# ICM-20948.net
KiCad netlist of a schematic drawn in Altium Designer
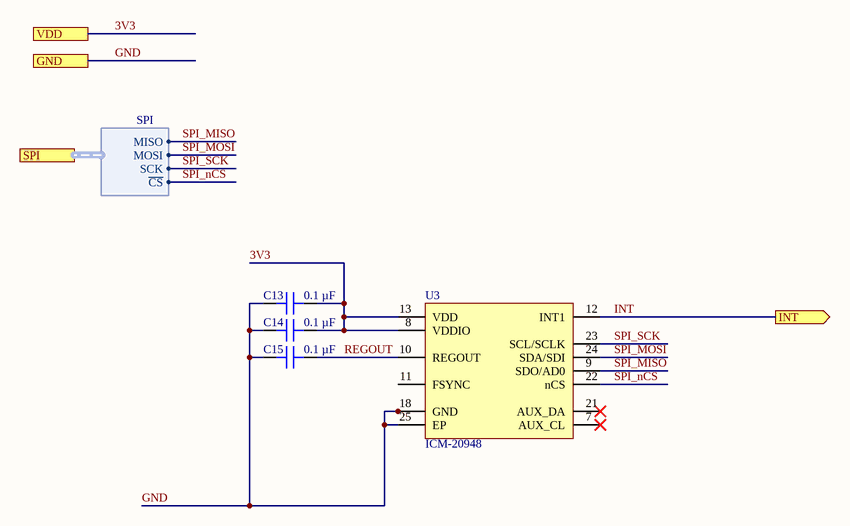
[diagram p0: ICM-20948.SchDoc]

(export (version "E")
  (design (tool "Eeschema 10.0.6"))
  (components
    (comp (ref "C13")
      (value "0.1 µF")
      (footprint "CAP 0402_1005")
      (description "CAP CER 0.1UF 16V X7R 0402")
      (fields (field (name "PART NUMBER") "C0402C104K4RACAUTO") (field (name "MANUFACTURER") "KEMET"))
      (libsource (lib "Celestial Altium Library - altium_library") (part "Capacitor"))
    )
    (comp (ref "C14")
      (value "0.1 µF")
      (footprint "CAP 0402_1005")
      (description "CAP CER 0.1UF 16V X7R 0402")
      (fields (field (name "PART NUMBER") "C0402C104K4RACAUTO") (field (name "MANUFACTURER") "KEMET"))
      (libsource (lib "Celestial Altium Library - altium_library") (part "Capacitor"))
    )
    (comp (ref "C15")
      (value "0.1 µF")
      (footprint "CAP 0402_1005")
      (description "CAP CER 0.1UF 16V X7R 0402")
      (fields (field (name "PART NUMBER") "C0402C104K4RACAUTO") (field (name "MANUFACTURER") "KEMET"))
      (libsource (lib "Celestial Altium Library - altium_library") (part "Capacitor"))
    )
    (comp (ref "U3")
      (value "ICM-20948")
      (footprint "ICM-20948")
      (description "9-DOF IMU")
      (libsource (lib "IC") (part "ICM-20948"))
    )
  )
  (nets
    (net (code "2") (name "/3V3") (class "Default")
      (node (ref "C13") (pin "1") (pinfunction "1_1") (pintype "passive"))
      (node (ref "C14") (pin "1") (pinfunction "1_1") (pintype "passive"))
      (node (ref "U3") (pin "13") (pinfunction "VDD_13") (pintype "passive"))
      (node (ref "U3") (pin "8") (pinfunction "VDDIO_8") (pintype "passive"))
    )
    (net (code "3") (name "/GND") (class "Default")
      (node (ref "C13") (pin "2") (pinfunction "2_2") (pintype "passive"))
      (node (ref "C14") (pin "2") (pinfunction "2_2") (pintype "passive"))
      (node (ref "C15") (pin "2") (pinfunction "2_2") (pintype "passive"))
      (node (ref "U3") (pin "18") (pinfunction "GND_18") (pintype "passive"))
      (node (ref "U3") (pin "20") (pinfunction "GND_20") (pintype "passive"))
      (node (ref "U3") (pin "25") (pinfunction "EP_25") (pintype "passive"))
    )
    (net (code "4") (name "/INT") (class "Default")
      (node (ref "U3") (pin "12") (pinfunction "INT1_12") (pintype "passive"))
    )
    (net (code "5") (name "/REGOUT") (class "Default")
      (node (ref "C15") (pin "1") (pinfunction "1_1") (pintype "passive"))
      (node (ref "U3") (pin "10") (pinfunction "REGOUT_10") (pintype "passive"))
    )
    (net (code "6") (name "/SPI_MISO") (class "Default")
      (node (ref "U3") (pin "9") (pinfunction "SDO/AD0_9") (pintype "passive"))
    )
    (net (code "7") (name "/SPI_MOSI") (class "Default")
      (node (ref "U3") (pin "24") (pinfunction "SDA/SDI_24") (pintype "passive"))
    )
    (net (code "8") (name "/SPI_SCK") (class "Default")
      (node (ref "U3") (pin "23") (pinfunction "SCL/SCLK_23") (pintype "passive"))
    )
    (net (code "9") (name "/SPI_nCS") (class "Default")
      (node (ref "U3") (pin "22") (pinfunction "nCS_22") (pintype "passive"))
    )
    (net (code "11") (name "unconnected-(U3-AUX_CL-Pad7)") (class "Default")
      (node (ref "U3") (pin "7") (pinfunction "AUX_CL_7") (pintype "passive+no_connect"))
    )
    (net (code "12") (name "unconnected-(U3-AUX_DA-Pad21)") (class "Default")
      (node (ref "U3") (pin "21") (pinfunction "AUX_DA_21") (pintype "passive+no_connect"))
    )
    (net (code "13") (name "unconnected-(U3-FSYNC-Pad11)") (class "Default")
      (node (ref "U3") (pin "11") (pinfunction "FSYNC_11") (pintype "passive"))
    )
  )
)
